# SD.net
KiCad netlist of a schematic drawn in Altium Designer
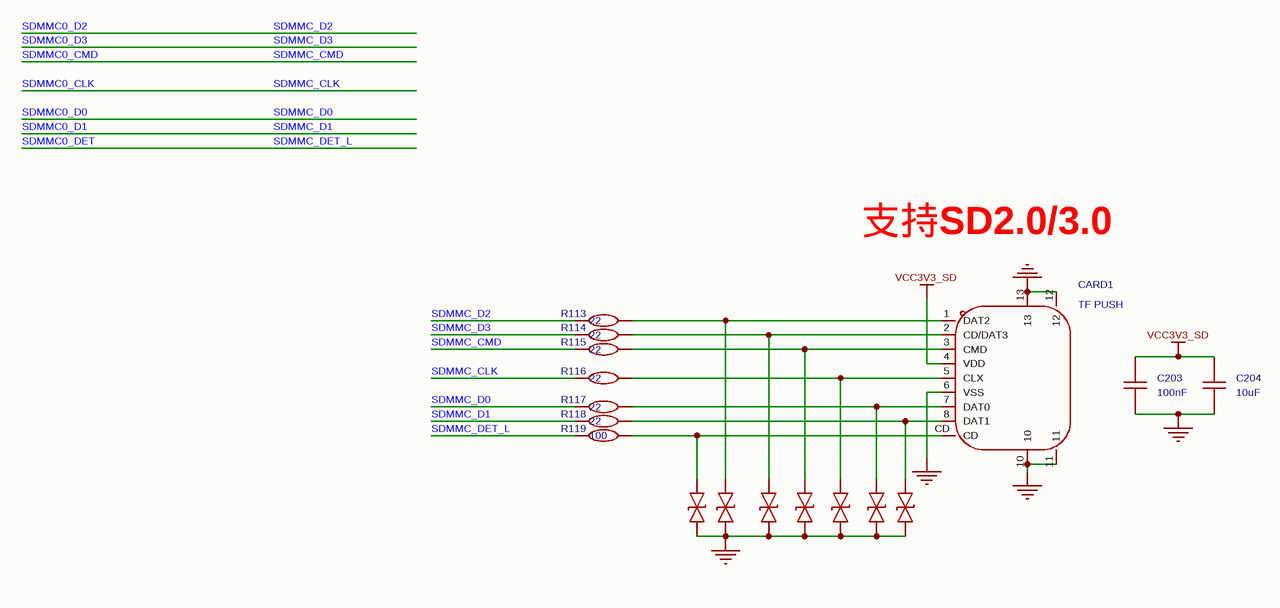
[diagram p0: SD.schdoc]

(export (version "E")
  (design (tool "Eeschema 10.0.6"))
  (components
    (comp (ref "C203")
      (value "100nF")
      (footprint "C0603")
      (libsource (lib "altium-import") (part "root_1_CAP_0603_"))
    )
    (comp (ref "C204")
      (value "10uF")
      (footprint "MYC0402")
      (description "容值:1uF;精度:±10%;额定电压:50V;材质(温度系数):X5R;")
      (fields (field (name "MANUFACTURER") "SAMSUNG(三星)") (field (name "MANUFACTURERPART") "CL10A105KB8NNNC"))
      (libsource (lib "altium-import") (part "root_3_CL10A105KB8NNNC_"))
    )
    (comp (ref "CARD1")
      (value "TF PUSH")
      (footprint "TF-SMD_TF-PUSH")
      (description "卡连接方式:自弹式;卡类型:MicroSD卡(TF卡);连接器类型:卡座;本体最大高度:2mm;工作温度范围:-20℃~+90℃;")
      (fields (field (name "MANUFACTURER") "SHOU HAN(首韩)"))
      (libsource (lib "altium-import") (part "root_0_TF PUSH_"))
    )
    (comp (ref "R113")
      (value "22")
      (footprint "R0402")
      (libsource (lib "altium-import") (part "root_0_Res_0402_"))
    )
    (comp (ref "R114")
      (value "22")
      (footprint "R0402")
      (libsource (lib "altium-import") (part "root_0_Res_0402_"))
    )
    (comp (ref "R115")
      (value "22")
      (footprint "R0402")
      (libsource (lib "altium-import") (part "root_0_Res_0402_"))
    )
    (comp (ref "R116")
      (value "22")
      (footprint "R0402")
      (libsource (lib "altium-import") (part "root_0_Res_0402_"))
    )
    (comp (ref "R117")
      (value "22")
      (footprint "R0402")
      (libsource (lib "altium-import") (part "root_0_Res_0402_"))
    )
    (comp (ref "R118")
      (value "22")
      (footprint "R0402")
      (libsource (lib "altium-import") (part "root_0_Res_0402_"))
    )
    (comp (ref "R119")
      (value "100")
      (footprint "R0402")
      (libsource (lib "altium-import") (part "root_0_Res_0402_"))
    )
    (comp (ref "U14")
      (value "ESD5341N")
      (footprint "DFN1006-2L-BI")
      (fields (field (name "MANUFACTURER") "KUU"))
      (libsource (lib "altium-import") (part "root_1_ESD5341N_C20612964_"))
    )
    (comp (ref "U15")
      (value "ESD5341N")
      (footprint "DFN1006-2L-BI")
      (fields (field (name "MANUFACTURER") "KUU"))
      (libsource (lib "altium-import") (part "root_1_ESD5341N_C20612964_"))
    )
    (comp (ref "U16")
      (value "ESD5341N")
      (footprint "DFN1006-2L-BI")
      (fields (field (name "MANUFACTURER") "KUU"))
      (libsource (lib "altium-import") (part "root_1_ESD5341N_C20612964_"))
    )
    (comp (ref "U17")
      (value "ESD5341N")
      (footprint "DFN1006-2L-BI")
      (fields (field (name "MANUFACTURER") "KUU"))
      (libsource (lib "altium-import") (part "root_1_ESD5341N_C20612964_"))
    )
    (comp (ref "U18")
      (value "ESD5341N")
      (footprint "DFN1006-2L-BI")
      (fields (field (name "MANUFACTURER") "KUU"))
      (libsource (lib "altium-import") (part "root_1_ESD5341N_C20612964_"))
    )
    (comp (ref "U19")
      (value "ESD5341N")
      (footprint "DFN1006-2L-BI")
      (fields (field (name "MANUFACTURER") "KUU"))
      (libsource (lib "altium-import") (part "root_1_ESD5341N_C20612964_"))
    )
    (comp (ref "U20")
      (value "ESD5341N")
      (footprint "DFN1006-2L-BI")
      (fields (field (name "MANUFACTURER") "KUU"))
      (libsource (lib "altium-import") (part "root_1_ESD5341N_C20612964_"))
    )
  )
  (nets
    (net (code "1") (name "/SDMMC0_CLK") (class "Default")
      (node (ref "R116") (pin "1") (pinfunction "1_1") (pintype "passive"))
    )
    (net (code "2") (name "/SDMMC0_CMD") (class "Default")
      (node (ref "R115") (pin "1") (pinfunction "1_1") (pintype "passive"))
    )
    (net (code "3") (name "/SDMMC0_D0") (class "Default")
      (node (ref "R117") (pin "1") (pinfunction "1_1") (pintype "passive"))
    )
    (net (code "4") (name "/SDMMC0_D1") (class "Default")
      (node (ref "R118") (pin "1") (pinfunction "1_1") (pintype "passive"))
    )
    (net (code "5") (name "/SDMMC0_D2") (class "Default")
      (node (ref "R113") (pin "1") (pinfunction "1_1") (pintype "passive"))
    )
    (net (code "6") (name "/SDMMC0_D3") (class "Default")
      (node (ref "R114") (pin "1") (pinfunction "1_1") (pintype "passive"))
    )
    (net (code "7") (name "/SDMMC0_DET") (class "Default")
      (node (ref "R119") (pin "1") (pinfunction "1_1") (pintype "passive"))
    )
    (net (code "8") (name "GND") (class "Default")
      (node (ref "C203") (pin "1") (pinfunction "1_1") (pintype "passive"))
      (node (ref "C204") (pin "2") (pinfunction "2_2") (pintype "passive"))
      (node (ref "CARD1") (pin "10") (pinfunction "10_10") (pintype "passive"))
      (node (ref "CARD1") (pin "11") (pinfunction "11_11") (pintype "passive"))
      (node (ref "CARD1") (pin "12") (pinfunction "12_12") (pintype "passive"))
      (node (ref "CARD1") (pin "13") (pinfunction "13_13") (pintype "passive"))
      (node (ref "CARD1") (pin "6") (pinfunction "VSS_6") (pintype "passive"))
      (node (ref "U14") (pin "1") (pinfunction "1_1") (pintype "passive"))
      (node (ref "U15") (pin "1") (pinfunction "1_1") (pintype "passive"))
      (node (ref "U16") (pin "1") (pinfunction "1_1") (pintype "passive"))
      (node (ref "U17") (pin "1") (pinfunction "1_1") (pintype "passive"))
      (node (ref "U18") (pin "1") (pinfunction "1_1") (pintype "passive"))
      (node (ref "U19") (pin "1") (pinfunction "1_1") (pintype "passive"))
      (node (ref "U20") (pin "1") (pinfunction "1_1") (pintype "passive"))
    )
    (net (code "9") (name "Net-(CARD1-CD{slash}DAT3)") (class "Default")
      (node (ref "CARD1") (pin "2") (pinfunction "CD/DAT3_2") (pintype "passive"))
      (node (ref "R114") (pin "2") (pinfunction "2_2") (pintype "passive"))
      (node (ref "U16") (pin "2") (pinfunction "2_2") (pintype "passive"))
    )
    (net (code "10") (name "Net-(CARD1-CLX)") (class "Default")
      (node (ref "CARD1") (pin "5") (pinfunction "CLX_5") (pintype "passive"))
      (node (ref "R116") (pin "2") (pinfunction "2_2") (pintype "passive"))
      (node (ref "U18") (pin "2") (pinfunction "2_2") (pintype "passive"))
    )
    (net (code "11") (name "Net-(CARD1-CMD)") (class "Default")
      (node (ref "CARD1") (pin "3") (pinfunction "CMD_3") (pintype "passive"))
      (node (ref "R115") (pin "2") (pinfunction "2_2") (pintype "passive"))
      (node (ref "U17") (pin "2") (pinfunction "2_2") (pintype "passive"))
    )
    (net (code "12") (name "Net-(CARD1-DAT0)") (class "Default")
      (node (ref "CARD1") (pin "7") (pinfunction "DAT0_7") (pintype "passive"))
      (node (ref "R117") (pin "2") (pinfunction "2_2") (pintype "passive"))
      (node (ref "U19") (pin "2") (pinfunction "2_2") (pintype "passive"))
    )
    (net (code "13") (name "Net-(CARD1-DAT1)") (class "Default")
      (node (ref "CARD1") (pin "8") (pinfunction "DAT1_8") (pintype "passive"))
      (node (ref "R118") (pin "2") (pinfunction "2_2") (pintype "passive"))
      (node (ref "U20") (pin "2") (pinfunction "2_2") (pintype "passive"))
    )
    (net (code "14") (name "Net-(CARD1-DAT2)") (class "Default")
      (node (ref "CARD1") (pin "1") (pinfunction "DAT2_1") (pintype "passive"))
      (node (ref "R113") (pin "2") (pinfunction "2_2") (pintype "passive"))
      (node (ref "U15") (pin "2") (pinfunction "2_2") (pintype "passive"))
    )
    (net (code "15") (name "Net-(CARD1-PadCD)") (class "Default")
      (node (ref "CARD1") (pin "CD") (pinfunction "CD_CD") (pintype "passive"))
      (node (ref "R119") (pin "2") (pinfunction "2_2") (pintype "passive"))
      (node (ref "U14") (pin "2") (pinfunction "2_2") (pintype "passive"))
    )
    (net (code "16") (name "VCC3V3_SD") (class "Default")
      (node (ref "C203") (pin "2") (pinfunction "2_2") (pintype "passive"))
      (node (ref "C204") (pin "1") (pinfunction "1_1") (pintype "passive"))
      (node (ref "CARD1") (pin "4") (pinfunction "VDD_4") (pintype "passive"))
    )
  )
)
